# Connectors.net
KiCad netlist of a schematic drawn in Altium Designer
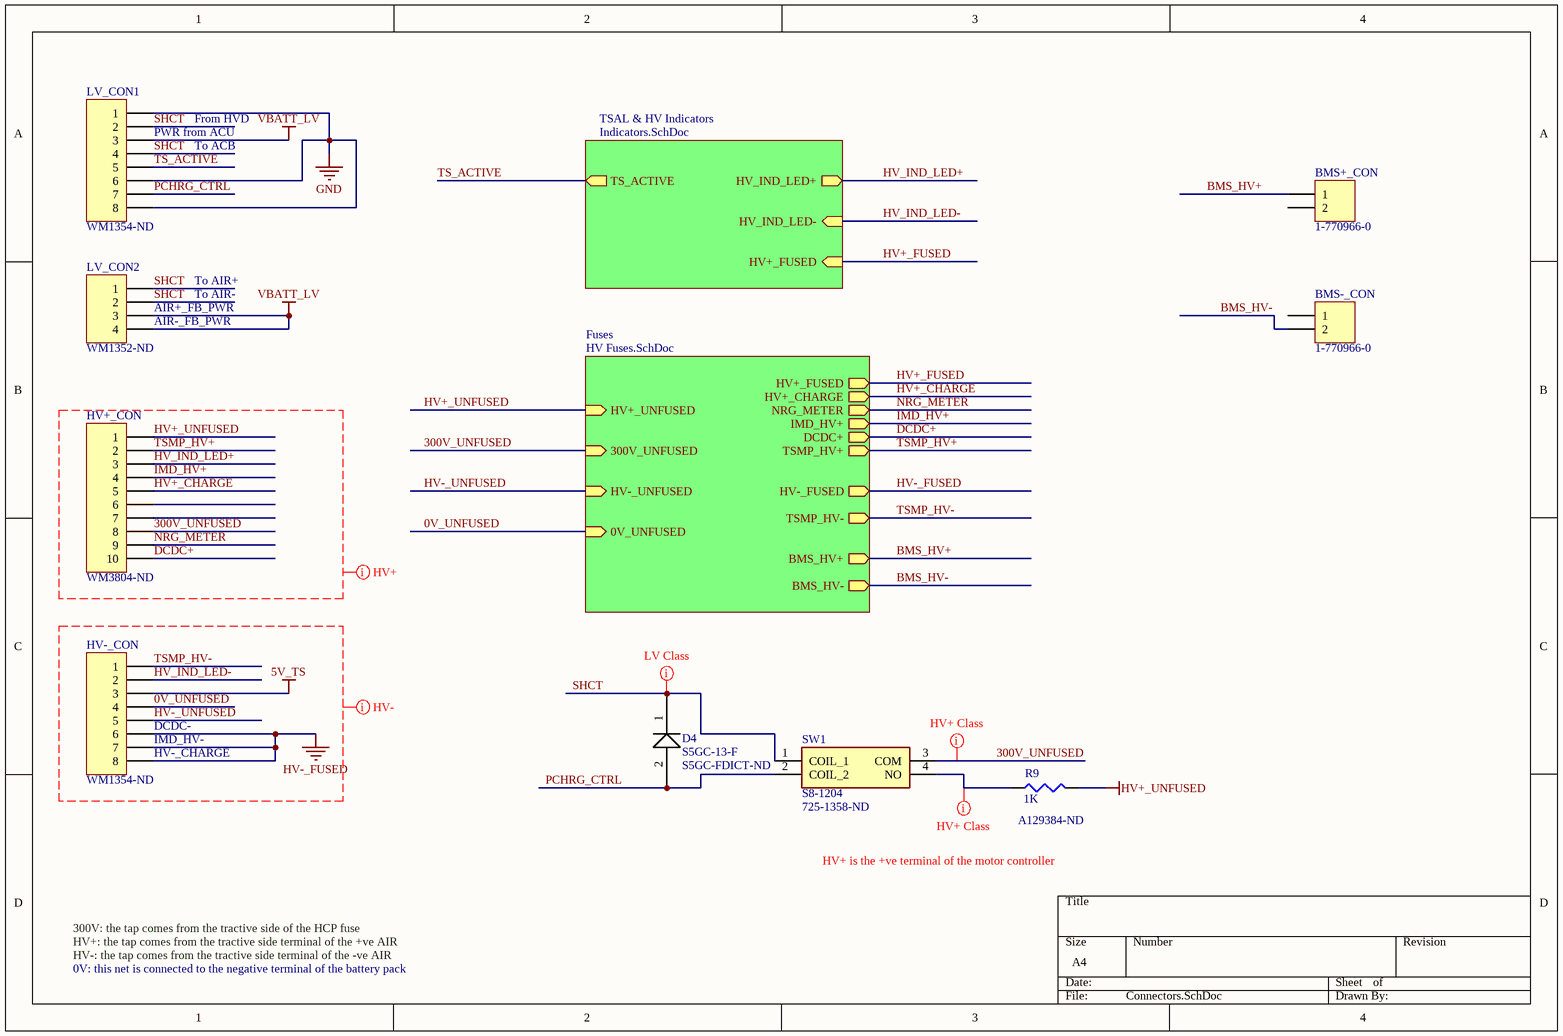
[diagram p0: Connectors.SchDoc]

(export (version "E")
  (design (tool "Eeschema 10.0.6"))
  (components
    (comp (ref "BMS+_CON")
      (value "1-770966-0")
      (footprint "TE  1-770966-0 2POS CONN")
      (description "Header, 2-Pin")
      (fields (field (name "PUBLISHER") "Altium Limited"))
      (libsource (lib "Miscellaneous Connectors") (part "Header 2"))
    )
    (comp (ref "BMS-_CON")
      (value "1-770966-0")
      (footprint "TE  1-770966-0 2POS CONN")
      (description "Header, 2-Pin")
      (fields (field (name "PUBLISHER") "Altium Limited"))
      (libsource (lib "Miscellaneous Connectors") (part "Header 2"))
    )
    (comp (ref "D4")
      (value "S5GC-13-F")
      (footprint "DO-214AB")
      (description "DIODE GEN PURP 400V 5A SMC")
      (fields (field (name "SUPPLIER PART NUMBER 1") "S5GC-FDICT-ND"))
      (libsource (lib "FE Schem Lib") (part "DIODE 1N4001"))
    )
    (comp (ref "HV+_CON")
      (value "~")
      (footprint "WM3804-ND")
      (description "WM3804-ND")
      (fields (field (name "SUPPLIER PART NUMBER 1") "WM3804-ND") (field (name "PUBLISHER") "Altium Limited"))
      (libsource (lib "Miscellaneous Connectors") (part "Header 10"))
    )
    (comp (ref "HV-_CON")
      (value "Header 8")
      (footprint "WM3846-ND")
      (description "Header, 8-Pin")
      (fields (field (name "SUPPLIER PART NUMBER 1") "WM1354-ND") (field (name "PUBLISHER") "Altium Limited"))
      (libsource (lib "Miscellaneous Connectors") (part "Header 8"))
    )
    (comp (ref "LV_CON1")
      (value "Header 8")
      (footprint "WM3846-ND")
      (description "Header, 8-Pin")
      (fields (field (name "SUPPLIER PART NUMBER 1") "WM1354-ND") (field (name "PUBLISHER") "Altium Limited"))
      (libsource (lib "Miscellaneous Connectors") (part "Header 8"))
    )
    (comp (ref "LV_CON2")
      (value "Header 4")
      (footprint "WM3801-ND")
      (description "Header, 4-Pin")
      (fields (field (name "SUPPLIER PART NUMBER 1") "WM1352-ND") (field (name "PUBLISHER") "Altium Limited"))
      (libsource (lib "Miscellaneous Connectors") (part "Header 4"))
    )
    (comp (ref "R9")
      (value "1K")
      (footprint "AXIAL RESISTOR WW 14W")
      (description "20J1K0E: RES 1K OHM 10W 5% AXIAL")
      (fields
        (field (name "SUPPLIER PART NUMBER 1") "A129384-ND")
        (field (name "PUBLISHER") "Altium Limited")
      )
      (libsource (lib "Miscellaneous Devices") (part "Res3"))
    )
    (comp (ref "SW1")
      (value "S8-1204")
      (footprint "SamacSys:S80504VU")
      (description "Relay or Contactor")
      (fields
        (field (name "MANUFACTURER_PART_NUMBER") "S8-1204V/RS")
        (field (name "RS PART NUMBER") "1245064")
        (field (name "SUPPLIER PART NUMBER 1") "725-1358-ND")
      )
      (libsource (lib "*") (part "S8-1204V_RS"))
    )
  )
  (nets
    (net (code "1") (name "/0V_UNFUSED") (class "Default")
      (node (ref "HV-_CON") (pin "4") (pinfunction "4_4") (pintype "passive"))
    )
    (net (code "2") (name "/300V_UNFUSED") (class "Default")
      (node (ref "HV+_CON") (pin "8") (pinfunction "8_8") (pintype "passive"))
      (node (ref "SW1") (pin "3") (pinfunction "COM_3") (pintype "passive"))
    )
    (net (code "3") (name "/BMS_HV+") (class "Default")
      (node (ref "BMS+_CON") (pin "1") (pinfunction "1_1") (pintype "passive"))
    )
    (net (code "4") (name "/BMS_HV-") (class "Default")
      (node (ref "BMS-_CON") (pin "2") (pinfunction "2_2") (pintype "passive"))
    )
    (net (code "5") (name "/DCDC+") (class "Default")
      (node (ref "HV+_CON") (pin "10") (pinfunction "10_10") (pintype "passive"))
    )
    (net (code "6") (name "/HV+_CHARGE") (class "Default")
      (node (ref "HV+_CON") (pin "5") (pinfunction "5_5") (pintype "passive"))
    )
    (net (code "8") (name "/HV-_UNFUSED") (class "Default")
      (node (ref "HV-_CON") (pin "5") (pinfunction "5_5") (pintype "passive"))
    )
    (net (code "9") (name "/HV_IND_LED+") (class "Default")
      (node (ref "HV+_CON") (pin "3") (pinfunction "3_3") (pintype "passive"))
    )
    (net (code "10") (name "/HV_IND_LED-") (class "Default")
      (node (ref "HV-_CON") (pin "2") (pinfunction "2_2") (pintype "passive"))
    )
    (net (code "11") (name "/IMD_HV+") (class "Default")
      (node (ref "HV+_CON") (pin "4") (pinfunction "4_4") (pintype "passive"))
    )
    (net (code "12") (name "/NRG_METER") (class "Default")
      (node (ref "HV+_CON") (pin "9") (pinfunction "9_9") (pintype "passive"))
    )
    (net (code "13") (name "/PCHRG_CTRL") (class "Default")
      (node (ref "D4") (pin "2") (pinfunction "2_2") (pintype "passive"))
      (node (ref "LV_CON1") (pin "7") (pinfunction "7_7") (pintype "passive"))
      (node (ref "SW1") (pin "2") (pinfunction "COIL_2_2") (pintype "passive"))
    )
    (net (code "14") (name "/SHCT") (class "Default")
      (node (ref "D4") (pin "1") (pinfunction "1_1") (pintype "passive"))
      (node (ref "LV_CON1") (pin "2") (pinfunction "2_2") (pintype "passive"))
      (node (ref "LV_CON1") (pin "4") (pinfunction "4_4") (pintype "passive"))
      (node (ref "LV_CON2") (pin "1") (pinfunction "1_1") (pintype "passive"))
      (node (ref "LV_CON2") (pin "2") (pinfunction "2_2") (pintype "passive"))
      (node (ref "SW1") (pin "1") (pinfunction "COIL_1_1") (pintype "passive"))
    )
    (net (code "15") (name "/TSMP_HV+") (class "Default")
      (node (ref "HV+_CON") (pin "2") (pinfunction "2_2") (pintype "passive"))
    )
    (net (code "16") (name "/TSMP_HV-") (class "Default")
      (node (ref "HV-_CON") (pin "1") (pinfunction "1_1") (pintype "passive"))
    )
    (net (code "17") (name "/TS_ACTIVE") (class "Default")
      (node (ref "LV_CON1") (pin "5") (pinfunction "5_5") (pintype "passive"))
    )
    (net (code "18") (name "5V_TS") (class "Default")
      (node (ref "HV-_CON") (pin "3") (pinfunction "3_3") (pintype "passive"))
    )
    (net (code "19") (name "GND") (class "Default")
      (node (ref "LV_CON1") (pin "1") (pinfunction "1_1") (pintype "passive"))
      (node (ref "LV_CON1") (pin "6") (pinfunction "6_6") (pintype "passive"))
      (node (ref "LV_CON1") (pin "8") (pinfunction "8_8") (pintype "passive"))
    )
    (net (code "20") (name "HV+_UNFUSED") (class "Default")
      (node (ref "HV+_CON") (pin "1") (pinfunction "1_1") (pintype "passive"))
      (node (ref "R9") (pin "2") (pinfunction "2_2") (pintype "passive"))
    )
    (net (code "21") (name "HV-_FUSED") (class "Default")
      (node (ref "HV-_CON") (pin "6") (pinfunction "6_6") (pintype "passive"))
      (node (ref "HV-_CON") (pin "7") (pinfunction "7_7") (pintype "passive"))
      (node (ref "HV-_CON") (pin "8") (pinfunction "8_8") (pintype "passive"))
    )
    (net (code "22") (name "Net-(SW1-NO)") (class "Default")
      (node (ref "R9") (pin "1") (pinfunction "1_1") (pintype "passive"))
      (node (ref "SW1") (pin "4") (pinfunction "NO_4") (pintype "passive"))
    )
    (net (code "23") (name "VBATT_LV") (class "Default")
      (node (ref "LV_CON1") (pin "3") (pinfunction "3_3") (pintype "passive"))
      (node (ref "LV_CON2") (pin "3") (pinfunction "3_3") (pintype "passive"))
      (node (ref "LV_CON2") (pin "4") (pinfunction "4_4") (pintype "passive"))
    )
    (net (code "24") (name "unconnected-(BMS+_CON-Pad2)") (class "Default")
      (node (ref "BMS+_CON") (pin "2") (pinfunction "2_2") (pintype "passive"))
    )
    (net (code "25") (name "unconnected-(BMS-_CON-Pad1)") (class "Default")
      (node (ref "BMS-_CON") (pin "1") (pinfunction "1_1") (pintype "passive"))
    )
    (net (code "26") (name "unconnected-(HV+_CON-Pad6)") (class "Default")
      (node (ref "HV+_CON") (pin "6") (pinfunction "6_6") (pintype "passive"))
    )
    (net (code "27") (name "unconnected-(HV+_CON-Pad7)") (class "Default")
      (node (ref "HV+_CON") (pin "7") (pinfunction "7_7") (pintype "passive"))
    )
  )
)
